# programmer_charger.net
KiCad netlist of a schematic drawn in Altium Designer
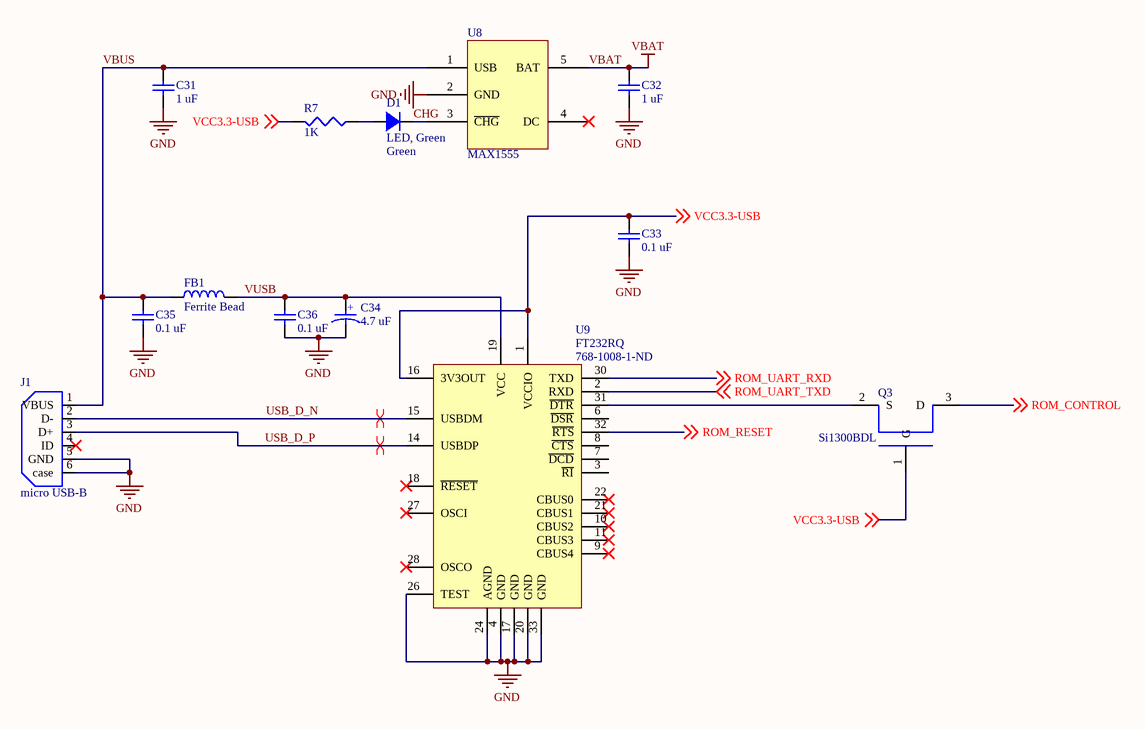
[diagram p0: programmer_charger.SchDoc]

(export (version "E")
  (design (tool "Eeschema 10.0.6"))
  (components
    (comp (ref "C31")
      (value "1 uF")
      (footprint "0402")
      (description "Ceramic capacitor, 1 uF, 0402 package")
      (fields (field (name "TOLERANCE") "10%") (field (name "Comment") "Ceramic capacitor"))
      (libsource (lib "rlc") (part "C_1u_0402_ceramic"))
    )
    (comp (ref "C32")
      (value "1 uF")
      (footprint "0402")
      (description "Ceramic capacitor, 1 uF, 0402 package")
      (fields (field (name "TOLERANCE") "10%") (field (name "Comment") "Ceramic capacitor"))
      (libsource (lib "rlc") (part "C_1u_0402_ceramic"))
    )
    (comp (ref "C33")
      (value "0.1 uF")
      (footprint "0402")
      (description "Ceramic capacitor, 0.1u, 0402 package")
      (fields (field (name "TOLERANCE") "10%") (field (name "Comment") "Ceramic capacitor"))
      (libsource (lib "rlc") (part "C_0.1u_0402_ceramic"))
    )
    (comp (ref "C34")
      (value "4.7 uF")
      (footprint "0603 - Polar Marking")
      (description "Tantalum capacitor, 4.7 uF, 0603 package")
      (fields (field (name "TOLERANCE") "20%") (field (name "Comment") "Tantalum capacitor"))
      (libsource (lib "rlc") (part "C_4.7u_0603_tantalum"))
    )
    (comp (ref "C35")
      (value "0.1 uF")
      (footprint "0402")
      (description "Ceramic capacitor, 0.1u, 0402 package")
      (fields (field (name "TOLERANCE") "10%") (field (name "Comment") "Ceramic capacitor"))
      (libsource (lib "rlc") (part "C_0.1u_0402_ceramic"))
    )
    (comp (ref "C36")
      (value "0.1 uF")
      (footprint "0402")
      (description "Ceramic capacitor, 0.1u, 0402 package")
      (fields (field (name "TOLERANCE") "10%") (field (name "Comment") "Ceramic capacitor"))
      (libsource (lib "rlc") (part "C_0.1u_0402_ceramic"))
    )
    (comp (ref "D1")
      (value "LED, Green")
      (footprint "0402 - DIODE")
      (description "LED, Green,  0402")
      (fields (field (name "COLOR") "Green"))
      (libsource (lib "rlc") (part "D_LED_GREEN_0402"))
    )
    (comp (ref "FB1")
      (value "Ferrite Bead")
      (footprint "0402")
      (description "Ferrite Bead, 150 mA, 0402 package")
      (libsource (lib "rlc") (part "FB_150mA_0402"))
    )
    (comp (ref "J1")
      (value "micro USB-B")
      (footprint "Micro USB-B")
      (description "CONN USB MICRO B RECPT SMT R/A")
      (libsource (lib "connectors") (part "Micro USB"))
    )
    (comp (ref "Q3")
      (value "Si1300BDL")
      (footprint "SC70-3")
      (description "MOSFET N-CH D-S 20V SC-70-3")
      (libsource (lib "opo_general") (part "Si1300BDL"))
    )
    (comp (ref "R7")
      (value "1K")
      (footprint "0402")
      (description "Chip resistor, 1K, 0402 package")
      (fields (field (name "TOLERANCE") "1%") (field (name "POWER") "1/16 W"))
      (libsource (lib "rlc") (part "R_1K_0402"))
    )
    (comp (ref "U8")
      (value "MAX1555")
      (footprint "SOT23-5")
      (description "3 Dual-Input USB/AC Adapter 1-Cell Li+  Battery Chargers")
      (libsource (lib "opo_general") (part "MAX1555"))
    )
    (comp (ref "U9")
      (value "FT232RQ")
      (footprint "QFN-32")
      (description "FT232R USB UART")
      (fields (field (name "SUPPLIER PART NUMBER 1") "768-1008-1-ND"))
      (libsource (lib "opo_general") (part "IC_FT232RQ"))
    )
  )
  (nets
    (net (code "1") (name "/CHG") (class "Default")
      (node (ref "D1") (pin "2") (pintype "passive"))
      (node (ref "U8") (pin "3") (pinfunction "~{CHG}_3") (pintype "passive"))
    )
    (net (code "2") (name "/USB_D_N") (class "Default")
      (node (ref "J1") (pin "2") (pinfunction "D-_2") (pintype "power_in"))
      (node (ref "U9") (pin "15") (pinfunction "USBDM_15") (pintype "passive"))
    )
    (net (code "3") (name "/USB_D_P") (class "Default")
      (node (ref "J1") (pin "3") (pinfunction "D+_3") (pintype "power_in"))
      (node (ref "U9") (pin "14") (pinfunction "USBDP_14") (pintype "passive"))
    )
    (net (code "4") (name "/VBUS") (class "Default")
      (node (ref "C31") (pin "1") (pintype "passive"))
      (node (ref "C35") (pin "1") (pintype "passive"))
      (node (ref "FB1") (pin "2") (pintype "passive"))
      (node (ref "J1") (pin "1") (pinfunction "VBUS_1") (pintype "power_in"))
      (node (ref "U8") (pin "1") (pinfunction "USB_1") (pintype "passive"))
    )
    (net (code "5") (name "/VUSB") (class "Default")
      (node (ref "C34") (pin "1") (pintype "passive"))
      (node (ref "C36") (pin "1") (pintype "passive"))
      (node (ref "FB1") (pin "1") (pintype "passive"))
      (node (ref "U9") (pin "19") (pinfunction "VCC_19") (pintype "passive"))
    )
    (net (code "6") (name "GND") (class "Default")
      (node (ref "C31") (pin "2") (pintype "passive"))
      (node (ref "C32") (pin "2") (pintype "passive"))
      (node (ref "C33") (pin "2") (pintype "passive"))
      (node (ref "C34") (pin "2") (pintype "passive"))
      (node (ref "C35") (pin "2") (pintype "passive"))
      (node (ref "C36") (pin "2") (pintype "passive"))
      (node (ref "J1") (pin "5") (pinfunction "GND_5") (pintype "power_in"))
      (node (ref "J1") (pin "6") (pinfunction "case_6") (pintype "power_in"))
      (node (ref "U8") (pin "2") (pinfunction "GND_2") (pintype "passive"))
      (node (ref "U9") (pin "17") (pinfunction "GND_17") (pintype "passive"))
      (node (ref "U9") (pin "20") (pinfunction "GND_20") (pintype "passive"))
      (node (ref "U9") (pin "24") (pinfunction "AGND_24") (pintype "passive"))
      (node (ref "U9") (pin "26") (pinfunction "TEST_26") (pintype "passive"))
      (node (ref "U9") (pin "33") (pinfunction "GND_33") (pintype "passive"))
      (node (ref "U9") (pin "4") (pinfunction "GND_4") (pintype "passive"))
    )
    (net (code "7") (name "Net-(D1-Pad1)") (class "Default")
      (node (ref "D1") (pin "1") (pintype "passive"))
      (node (ref "R7") (pin "2") (pintype "passive"))
    )
    (net (code "8") (name "Net-(Q3-S)") (class "Default")
      (node (ref "Q3") (pin "2") (pinfunction "S_2") (pintype "passive"))
      (node (ref "U9") (pin "31") (pinfunction "~{DTR}_31") (pintype "passive"))
    )
    (net (code "9") (name "ROM_CONTROL") (class "Default")
      (node (ref "Q3") (pin "3") (pinfunction "D_3") (pintype "passive"))
    )
    (net (code "10") (name "ROM_RESET") (class "Default")
      (node (ref "U9") (pin "32") (pinfunction "~{RTS}_32") (pintype "passive"))
    )
    (net (code "11") (name "ROM_UART_RXD") (class "Default")
      (node (ref "U9") (pin "30") (pinfunction "TXD_30") (pintype "passive"))
    )
    (net (code "12") (name "ROM_UART_TXD") (class "Default")
      (node (ref "U9") (pin "2") (pinfunction "RXD_2") (pintype "passive"))
    )
    (net (code "13") (name "VBAT") (class "Default")
      (node (ref "C32") (pin "1") (pintype "passive"))
      (node (ref "U8") (pin "5") (pinfunction "BAT_5") (pintype "passive"))
    )
    (net (code "14") (name "VCC3.3-USB") (class "Default")
      (node (ref "C33") (pin "1") (pintype "passive"))
      (node (ref "Q3") (pin "1") (pinfunction "G_1") (pintype "passive"))
      (node (ref "R7") (pin "1") (pintype "passive"))
      (node (ref "U9") (pin "1") (pinfunction "VCCIO_1") (pintype "passive"))
      (node (ref "U9") (pin "16") (pinfunction "3V3OUT_16") (pintype "passive"))
    )
    (net (code "15") (name "unconnected-(J1-ID-Pad4)") (class "Default")
      (node (ref "J1") (pin "4") (pinfunction "ID_4") (pintype "power_in+no_connect"))
    )
    (net (code "16") (name "unconnected-(U8-DC-Pad4)") (class "Default")
      (node (ref "U8") (pin "4") (pinfunction "DC_4") (pintype "passive+no_connect"))
    )
    (net (code "17") (name "unconnected-(U9-CBUS0-Pad22)") (class "Default")
      (node (ref "U9") (pin "22") (pinfunction "CBUS0_22") (pintype "passive+no_connect"))
    )
    (net (code "18") (name "unconnected-(U9-CBUS1-Pad21)") (class "Default")
      (node (ref "U9") (pin "21") (pinfunction "CBUS1_21") (pintype "passive+no_connect"))
    )
    (net (code "19") (name "unconnected-(U9-CBUS2-Pad10)") (class "Default")
      (node (ref "U9") (pin "10") (pinfunction "CBUS2_10") (pintype "passive+no_connect"))
    )
    (net (code "20") (name "unconnected-(U9-CBUS3-Pad11)") (class "Default")
      (node (ref "U9") (pin "11") (pinfunction "CBUS3_11") (pintype "passive+no_connect"))
    )
    (net (code "21") (name "unconnected-(U9-CBUS4-Pad9)") (class "Default")
      (node (ref "U9") (pin "9") (pinfunction "CBUS4_9") (pintype "passive+no_connect"))
    )
    (net (code "22") (name "unconnected-(U9-OSCI-Pad27)") (class "Default")
      (node (ref "U9") (pin "27") (pinfunction "OSCI_27") (pintype "passive+no_connect"))
    )
    (net (code "23") (name "unconnected-(U9-OSCO-Pad28)") (class "Default")
      (node (ref "U9") (pin "28") (pinfunction "OSCO_28") (pintype "passive+no_connect"))
    )
    (net (code "24") (name "unconnected-(U9-~{CTS}-Pad8)") (class "Default")
      (node (ref "U9") (pin "8") (pinfunction "~{CTS}_8") (pintype "passive"))
    )
    (net (code "25") (name "unconnected-(U9-~{DCD}-Pad7)") (class "Default")
      (node (ref "U9") (pin "7") (pinfunction "~{DCD}_7") (pintype "passive"))
    )
    (net (code "26") (name "unconnected-(U9-~{DSR}-Pad6)") (class "Default")
      (node (ref "U9") (pin "6") (pinfunction "~{DSR}_6") (pintype "passive"))
    )
    (net (code "27") (name "unconnected-(U9-~{RESET}-Pad18)") (class "Default")
      (node (ref "U9") (pin "18") (pinfunction "~{RESET}_18") (pintype "passive+no_connect"))
    )
    (net (code "28") (name "unconnected-(U9-~{RI}-Pad3)") (class "Default")
      (node (ref "U9") (pin "3") (pinfunction "~{RI}_3") (pintype "passive"))
    )
  )
)
